# rxsms-2_0-Stromvers.net
KiCad netlist of a schematic drawn in EAGLE
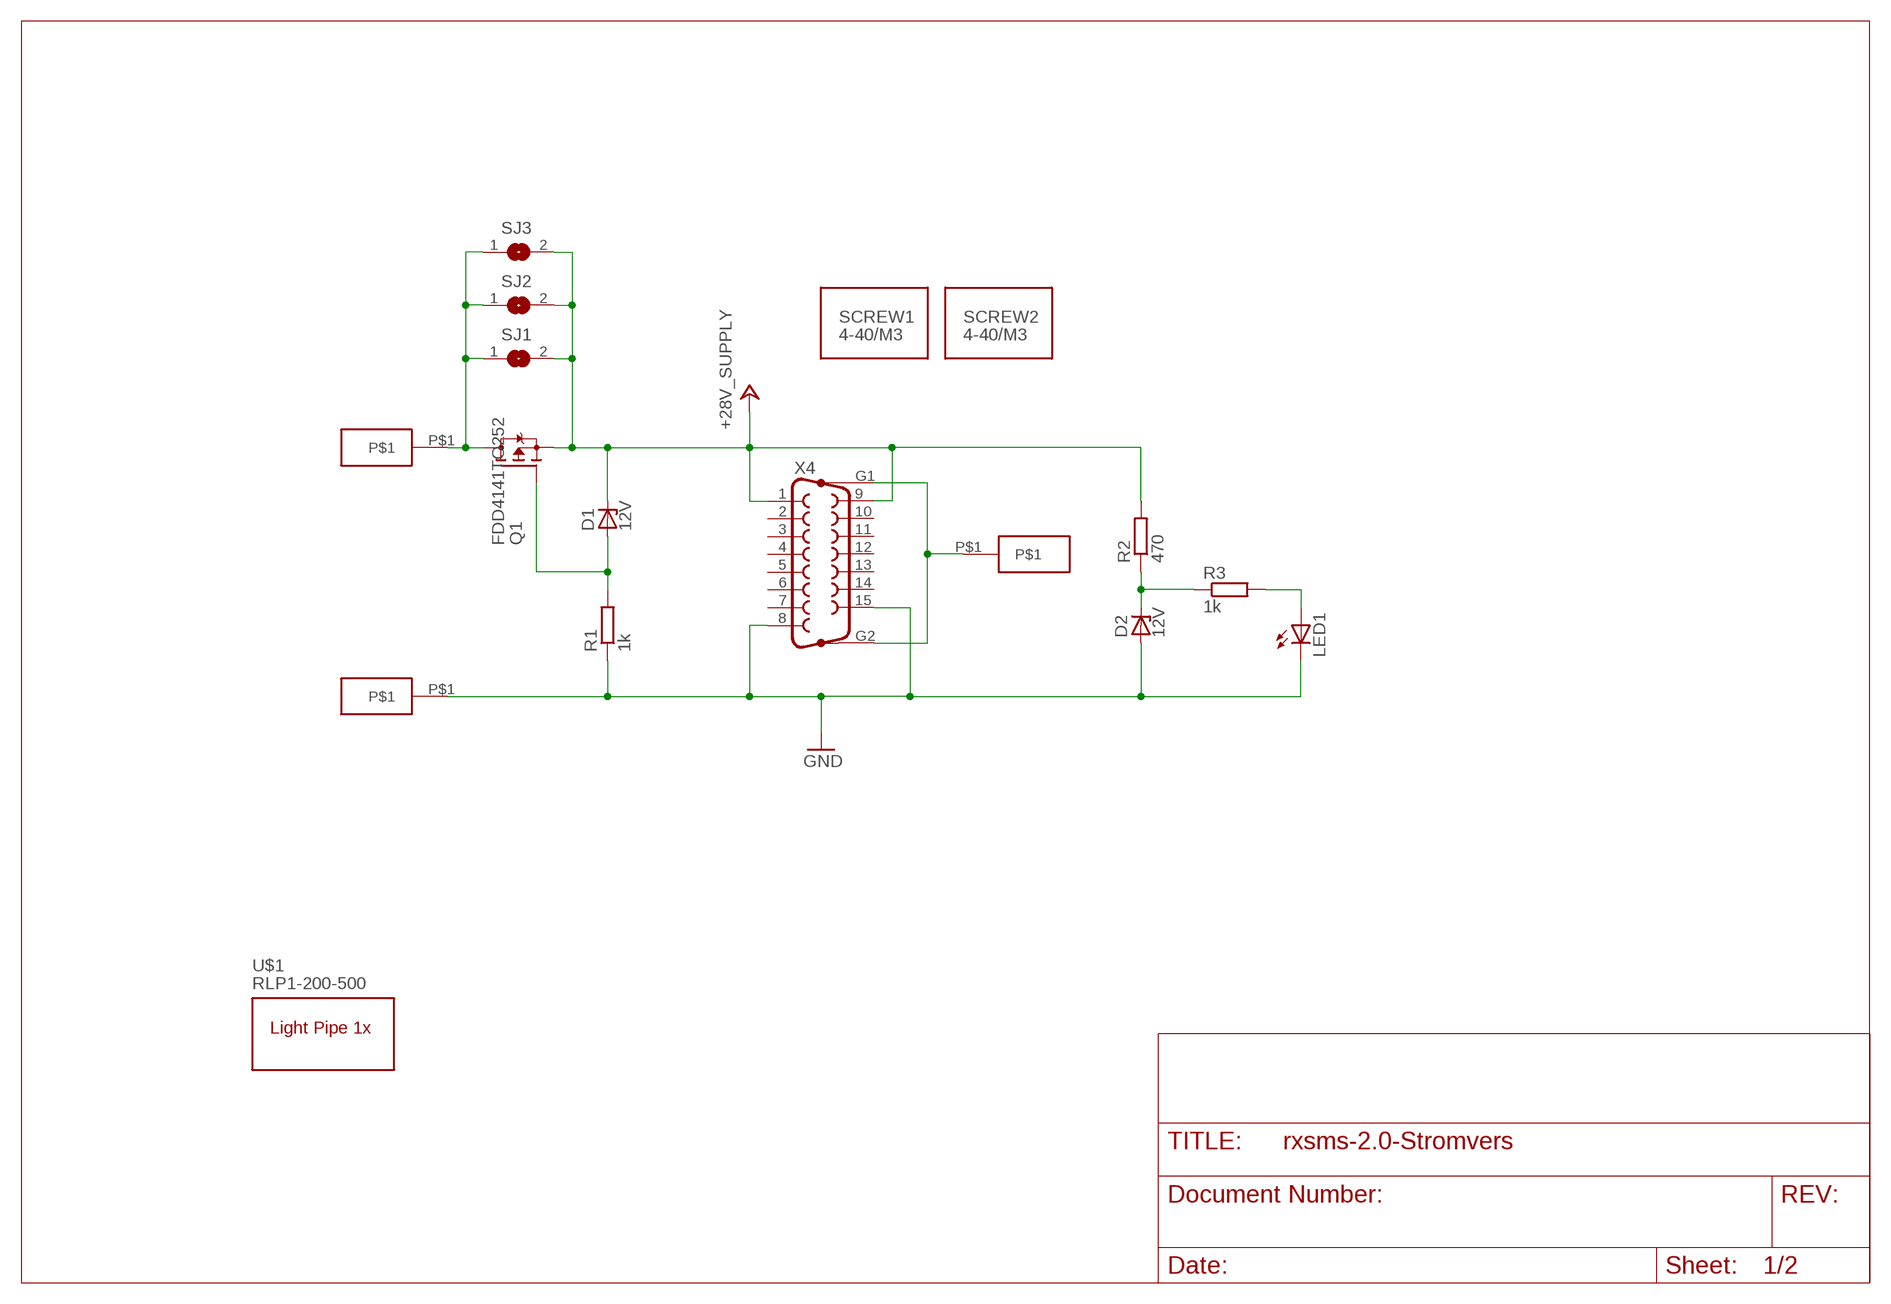
[diagram p0: schematic, sheet 1]
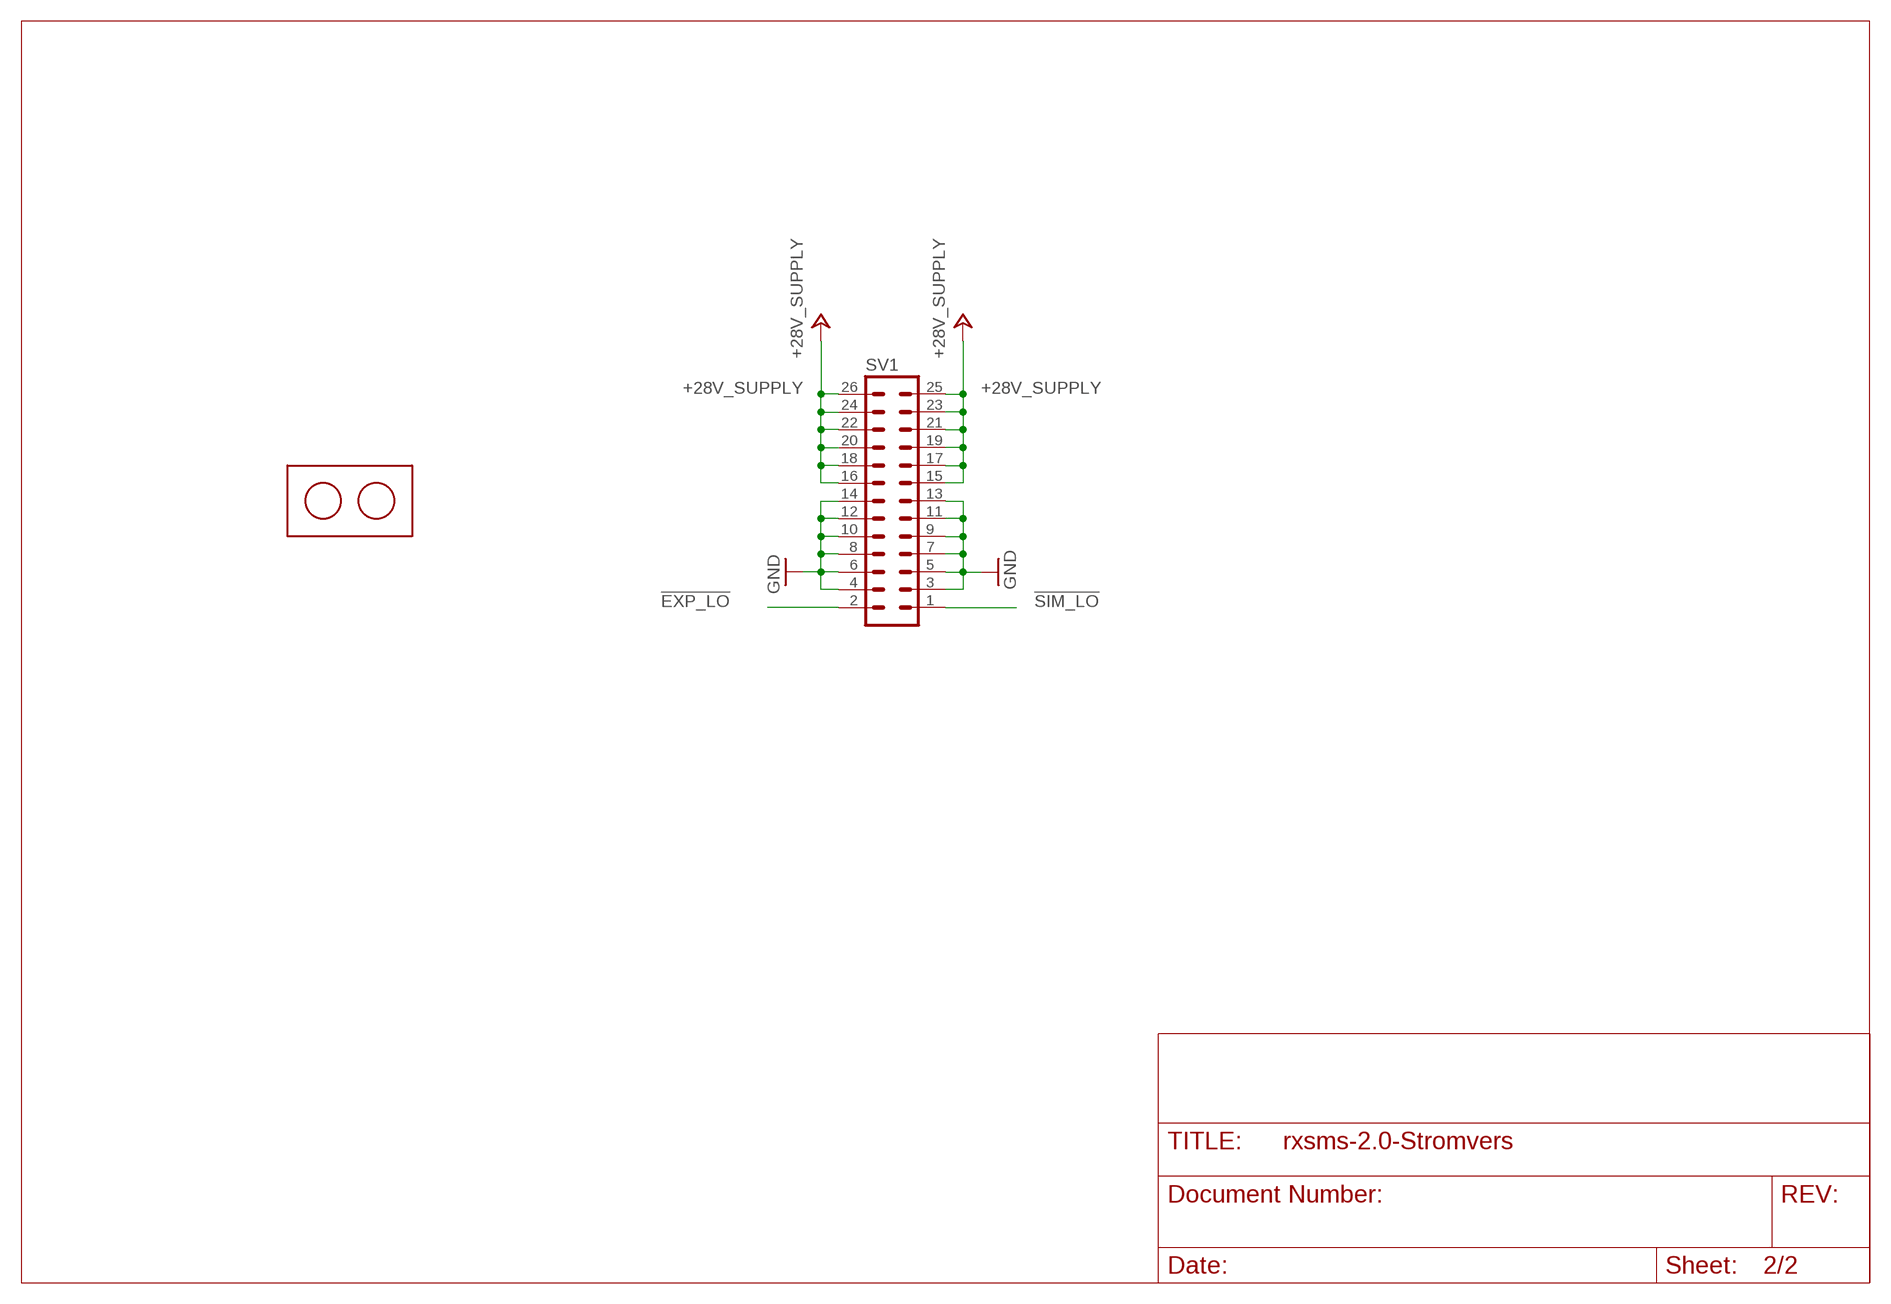
[diagram p1: schematic, sheet 2]

(export (version "E")
  (design (tool "Eeschema 10.0.6"))
  (components
    (comp (ref "D1")
      (value "12V")
      (footprint "eagle-import:DO34Z7")
      (libsource (lib "eagle-import") (part "ZENER-DIODEDO34-7"))
    )
    (comp (ref "D2")
      (value "12V")
      (footprint "eagle-import:DO34Z7")
      (libsource (lib "eagle-import") (part "ZENER-DIODEDO34-7"))
    )
    (comp (ref "LED1")
      (value "LEDCHIPLED_0805")
      (footprint "eagle-import:CHIPLED_0805")
      (libsource (lib "eagle-import") (part "LEDCHIPLED_0805"))
    )
    (comp (ref "Q1")
      (value "FDD4141TO252")
      (footprint "eagle-import:TO252")
      (libsource (lib "eagle-import") (part "FDD4141TO252"))
    )
    (comp (ref "R1")
      (value "1k")
      (footprint "eagle-import:R0805")
      (libsource (lib "eagle-import") (part "R-EU_R0805"))
    )
    (comp (ref "R2")
      (value "470")
      (footprint "eagle-import:R0805")
      (libsource (lib "eagle-import") (part "R-EU_R0805"))
    )
    (comp (ref "R3")
      (value "1k")
      (footprint "eagle-import:R0805")
      (libsource (lib "eagle-import") (part "R-EU_R0805"))
    )
    (comp (ref "SCREW1")
      (value "4-40/M3")
      (footprint "eagle-import:SCREW_DUMMY")
      (libsource (lib "eagle-import") (part "DSUB_MOUNTING_SCREW"))
    )
    (comp (ref "SCREW2")
      (value "4-40/M3")
      (footprint "eagle-import:SCREW_DUMMY")
      (libsource (lib "eagle-import") (part "DSUB_MOUNTING_SCREW"))
    )
    (comp (ref "SJ1") (value "SJ") (footprint "eagle-import:SJ") (libsource (lib "eagle-import") (part "SJ")))
    (comp (ref "SJ2") (value "SJ") (footprint "eagle-import:SJ") (libsource (lib "eagle-import") (part "SJ")))
    (comp (ref "SJ3") (value "SJ") (footprint "eagle-import:SJ") (libsource (lib "eagle-import") (part "SJ")))
    (comp (ref "U$1")
      (value "RLP1-200-500")
      (footprint "eagle-import:RLP1-200-500")
      (libsource (lib "eagle-import") (part "RLP1-200-500"))
    )
    (comp (ref "U$3")
      (value "JACK")
      (footprint "eagle-import:JACK")
      (libsource (lib "eagle-import") (part "JACK"))
    )
    (comp (ref "U$4")
      (value "JACK")
      (footprint "eagle-import:JACK")
      (libsource (lib "eagle-import") (part "JACK"))
    )
    (comp (ref "U$5")
      (value "JACK")
      (footprint "eagle-import:JACK")
      (libsource (lib "eagle-import") (part "JACK"))
    )
    (comp (ref "X4")
      (value "F15HP")
      (footprint "eagle-import:F15HP")
      (fields (field (name "OC_FARNELL") "1207598"))
      (libsource (lib "eagle-import") (part "F15HP"))
    )
    (comp (ref "SV1")
      (value "ML26L")
      (footprint "eagle-import:ML26L")
      (fields (field (name "OC_FARNELL") "1096983 (Gegenstück: 1200506 oder 1097038)"))
      (libsource (lib "eagle-import") (part "ML26L"))
    )
    (comp (ref "U$6")
      (value "BUERKLIN17H912")
      (footprint "eagle-import:BUERKLIN17H912")
      (libsource (lib "eagle-import") (part "BUERKLIN17H912"))
    )
  )
  (nets
    (net (code "1") (name "+28V_SUPPLY") (class "Default")
      (node (ref "D1") (pin "C") (pinfunction "C_C") (pintype "passive"))
      (node (ref "Q1") (pin "2") (pinfunction "S_2") (pintype "passive"))
      (node (ref "R2") (pin "2") (pinfunction "2_2") (pintype "passive"))
      (node (ref "SJ1") (pin "2") (pinfunction "2_2") (pintype "passive"))
      (node (ref "SJ2") (pin "2") (pinfunction "2_2") (pintype "passive"))
      (node (ref "SJ3") (pin "2") (pinfunction "2_2") (pintype "passive"))
      (node (ref "SV1") (pin "15") (pinfunction "15_15") (pintype "passive"))
      (node (ref "SV1") (pin "16") (pinfunction "16_16") (pintype "passive"))
      (node (ref "SV1") (pin "17") (pinfunction "17_17") (pintype "passive"))
      (node (ref "SV1") (pin "18") (pinfunction "18_18") (pintype "passive"))
      (node (ref "SV1") (pin "19") (pinfunction "19_19") (pintype "passive"))
      (node (ref "SV1") (pin "20") (pinfunction "20_20") (pintype "passive"))
      (node (ref "SV1") (pin "21") (pinfunction "21_21") (pintype "passive"))
      (node (ref "SV1") (pin "22") (pinfunction "22_22") (pintype "passive"))
      (node (ref "SV1") (pin "23") (pinfunction "23_23") (pintype "passive"))
      (node (ref "SV1") (pin "24") (pinfunction "24_24") (pintype "passive"))
      (node (ref "SV1") (pin "25") (pinfunction "25_25") (pintype "passive"))
      (node (ref "SV1") (pin "26") (pinfunction "26_26") (pintype "passive"))
      (node (ref "X4") (pin "1") (pinfunction "1_1") (pintype "passive"))
      (node (ref "X4") (pin "9") (pinfunction "9_9") (pintype "passive"))
    )
    (net (code "2") (name "GND") (class "Default")
      (node (ref "D2") (pin "A") (pinfunction "A_A") (pintype "passive"))
      (node (ref "LED1") (pin "C") (pinfunction "C_C") (pintype "passive"))
      (node (ref "R1") (pin "1") (pinfunction "1_1") (pintype "passive"))
      (node (ref "SV1") (pin "10") (pinfunction "10_10") (pintype "passive"))
      (node (ref "SV1") (pin "11") (pinfunction "11_11") (pintype "passive"))
      (node (ref "SV1") (pin "12") (pinfunction "12_12") (pintype "passive"))
      (node (ref "SV1") (pin "13") (pinfunction "13_13") (pintype "passive"))
      (node (ref "SV1") (pin "14") (pinfunction "14_14") (pintype "passive"))
      (node (ref "SV1") (pin "3") (pinfunction "3_3") (pintype "passive"))
      (node (ref "SV1") (pin "4") (pinfunction "4_4") (pintype "passive"))
      (node (ref "SV1") (pin "5") (pinfunction "5_5") (pintype "passive"))
      (node (ref "SV1") (pin "6") (pinfunction "6_6") (pintype "passive"))
      (node (ref "SV1") (pin "7") (pinfunction "7_7") (pintype "passive"))
      (node (ref "SV1") (pin "8") (pinfunction "8_8") (pintype "passive"))
      (node (ref "SV1") (pin "9") (pinfunction "9_9") (pintype "passive"))
      (node (ref "U$4") (pin "P$1") (pinfunction "P$1_P$1") (pintype "passive"))
      (node (ref "X4") (pin "15") (pinfunction "15_15") (pintype "passive"))
      (node (ref "X4") (pin "8") (pinfunction "8_8") (pintype "passive"))
    )
    (net (code "3") (name "Net-(D2-PadC)") (class "Default")
      (node (ref "D2") (pin "C") (pinfunction "C_C") (pintype "passive"))
      (node (ref "R2") (pin "1") (pinfunction "1_1") (pintype "passive"))
      (node (ref "R3") (pin "1") (pinfunction "1_1") (pintype "passive"))
    )
    (net (code "4") (name "Net-(LED1-PadA)") (class "Default")
      (node (ref "LED1") (pin "A") (pinfunction "A_A") (pintype "passive"))
      (node (ref "R3") (pin "2") (pinfunction "2_2") (pintype "passive"))
    )
    (net (code "5") (name "Net-(Q1-D)") (class "Default")
      (node (ref "Q1") (pin "3") (pinfunction "D_3") (pintype "passive"))
      (node (ref "SJ1") (pin "1") (pinfunction "1_1") (pintype "passive"))
      (node (ref "SJ2") (pin "1") (pinfunction "1_1") (pintype "passive"))
      (node (ref "SJ3") (pin "1") (pinfunction "1_1") (pintype "passive"))
      (node (ref "U$3") (pin "P$1") (pinfunction "P$1_P$1") (pintype "passive"))
    )
    (net (code "6") (name "Net-(Q1-G)") (class "Default")
      (node (ref "D1") (pin "A") (pinfunction "A_A") (pintype "passive"))
      (node (ref "Q1") (pin "1") (pinfunction "G_1") (pintype "passive"))
      (node (ref "R1") (pin "2") (pinfunction "2_2") (pintype "passive"))
    )
    (net (code "7") (name "Net-(U$5-PadP$1)") (class "Default")
      (node (ref "U$5") (pin "P$1") (pinfunction "P$1_P$1") (pintype "passive"))
      (node (ref "X4") (pin "G1") (pinfunction "G1_G1") (pintype "passive"))
      (node (ref "X4") (pin "G2") (pinfunction "G2_G2") (pintype "passive"))
    )
    (net (code "8") (name "unconnected-(X4-Pad2)") (class "Default")
      (node (ref "X4") (pin "2") (pinfunction "2_2") (pintype "passive"))
    )
    (net (code "9") (name "unconnected-(X4-Pad3)") (class "Default")
      (node (ref "X4") (pin "3") (pinfunction "3_3") (pintype "passive"))
    )
    (net (code "10") (name "unconnected-(X4-Pad4)") (class "Default")
      (node (ref "X4") (pin "4") (pinfunction "4_4") (pintype "passive"))
    )
    (net (code "11") (name "unconnected-(X4-Pad5)") (class "Default")
      (node (ref "X4") (pin "5") (pinfunction "5_5") (pintype "passive"))
    )
    (net (code "12") (name "unconnected-(X4-Pad6)") (class "Default")
      (node (ref "X4") (pin "6") (pinfunction "6_6") (pintype "passive"))
    )
    (net (code "13") (name "unconnected-(X4-Pad7)") (class "Default")
      (node (ref "X4") (pin "7") (pinfunction "7_7") (pintype "passive"))
    )
    (net (code "14") (name "unconnected-(X4-Pad10)") (class "Default")
      (node (ref "X4") (pin "10") (pinfunction "10_10") (pintype "passive"))
    )
    (net (code "15") (name "unconnected-(X4-Pad11)") (class "Default")
      (node (ref "X4") (pin "11") (pinfunction "11_11") (pintype "passive"))
    )
    (net (code "16") (name "unconnected-(X4-Pad12)") (class "Default")
      (node (ref "X4") (pin "12") (pinfunction "12_12") (pintype "passive"))
    )
    (net (code "17") (name "unconnected-(X4-Pad13)") (class "Default")
      (node (ref "X4") (pin "13") (pinfunction "13_13") (pintype "passive"))
    )
    (net (code "18") (name "unconnected-(X4-Pad14)") (class "Default")
      (node (ref "X4") (pin "14") (pinfunction "14_14") (pintype "passive"))
    )
    (net (code "19") (name "~{EXP_LO}") (class "Default")
      (node (ref "SV1") (pin "2") (pinfunction "2_2") (pintype "passive"))
    )
    (net (code "20") (name "~{SIM_LO}") (class "Default")
      (node (ref "SV1") (pin "1") (pinfunction "1_1") (pintype "passive"))
    )
  )
)
